# ch340c_esp32.net
KiCad netlist of a schematic drawn in EAGLE
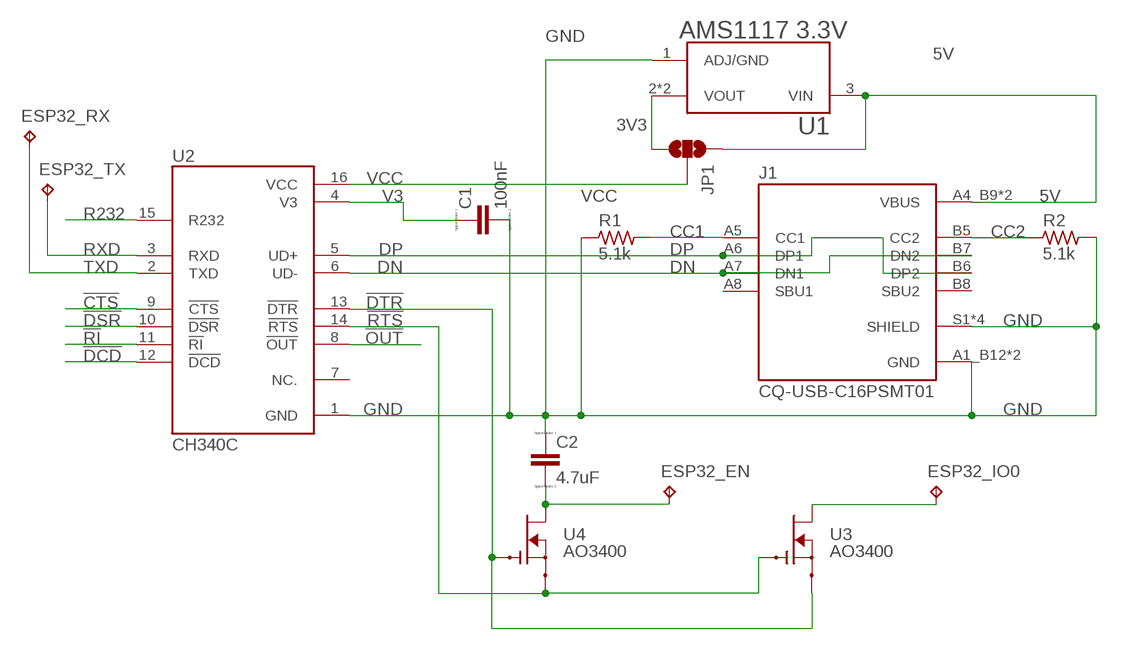
[diagram p0: schematic, sheet 1]

(export (version "E")
  (design (tool "Eeschema 10.0.6"))
  (components
    (comp (ref "C1")
      (value "100nF")
      (footprint "eagle-import:C0603")
      (libsource (lib "eagle-import") (part "CC0603"))
    )
    (comp (ref "C2")
      (value "4.7uF")
      (footprint "eagle-import:C0603")
      (libsource (lib "eagle-import") (part "CC0603"))
    )
    (comp (ref "ESP32_EN")
      (value "TPB1,27")
      (footprint "eagle-import:B1,27")
      (libsource (lib "eagle-import") (part "TPB1,27"))
    )
    (comp (ref "ESP32_IO0")
      (value "TPB1,27")
      (footprint "eagle-import:B1,27")
      (libsource (lib "eagle-import") (part "TPB1,27"))
    )
    (comp (ref "ESP32_RX")
      (value "TPB1,27")
      (footprint "eagle-import:B1,27")
      (libsource (lib "eagle-import") (part "TPB1,27"))
    )
    (comp (ref "ESP32_TX")
      (value "TPB1,27")
      (footprint "eagle-import:B1,27")
      (libsource (lib "eagle-import") (part "TPB1,27"))
    )
    (comp (ref "J1")
      (value "CQ-USB-C16PSMT01")
      (footprint "eagle-import:SHENZHEN-CHUANGQIN-TECHNOLOGY_CQ-USB-C16PSMT01")
      (fields (field (name "MF") "Shenzen Chuangqin Technology"))
      (libsource (lib "eagle-import") (part "CQ-USB-C16PSMT01"))
    )
    (comp (ref "JP1")
      (value "JUMPER-SMT_3_NO_NO-SILK")
      (footprint "eagle-import:SMT-JUMPER_3_NO_NO-SILK")
      (libsource (lib "eagle-import") (part "JUMPER-SMT_3_NO_NO-SILK"))
    )
    (comp (ref "R1")
      (value "5.1k")
      (footprint "eagle-import:RC-MASTER-SMD_R0603MP")
      (libsource (lib "eagle-import") (part "RC-MASTER-SMD_R_0603MP"))
    )
    (comp (ref "R2")
      (value "5.1k")
      (footprint "eagle-import:RC-MASTER-SMD_R0603MP")
      (libsource (lib "eagle-import") (part "RC-MASTER-SMD_R_0603MP"))
    )
    (comp (ref "U1")
      (value "AMS1117 3.3V")
      (footprint "eagle-import:SOT229P700X180-4N")
      (fields (field (name "MF") "Advanced Monolithic Systems") (field (name "MP") "AMS1117"))
      (libsource (lib "eagle-import") (part "AMS1117"))
    )
    (comp (ref "U2")
      (value "CH340C")
      (footprint "eagle-import:SOIC127P600X180-16N")
      (fields (field (name "MF") "WCH"))
      (libsource (lib "eagle-import") (part "CH340C"))
    )
    (comp (ref "U3")
      (value "AO3400")
      (footprint "eagle-import:SOT23")
      (fields (field (name "MF") "Alpha &"))
      (libsource (lib "eagle-import") (part "AO3400"))
    )
    (comp (ref "U4")
      (value "AO3400")
      (footprint "eagle-import:SOT23")
      (fields (field (name "MF") "Alpha &"))
      (libsource (lib "eagle-import") (part "AO3400"))
    )
  )
  (nets
    (net (code "1") (name "/3V3") (class "Default")
      (node (ref "JP1") (pin "1") (pinfunction "1_1") (pintype "passive"))
      (node (ref "U1") (pin "2") (pinfunction "VOUT_2") (pintype "output"))
      (node (ref "U1") (pin "4") (pinfunction "VOUT_4") (pintype "output"))
    )
    (net (code "2") (name "/5V") (class "Default")
      (node (ref "J1") (pin "A4_B9") (pinfunction "VBUS_A4_B9") (pintype "power_in"))
      (node (ref "J1") (pin "B4_A9") (pinfunction "VBUS_B4_A9") (pintype "power_in"))
      (node (ref "JP1") (pin "3") (pinfunction "3_3") (pintype "passive"))
      (node (ref "U1") (pin "3") (pinfunction "VIN_3") (pintype "input"))
    )
    (net (code "3") (name "/CC1") (class "Default")
      (node (ref "J1") (pin "A5") (pinfunction "CC1_A5") (pintype "bidirectional"))
      (node (ref "R1") (pin "2") (pinfunction "2_2") (pintype "passive"))
    )
    (net (code "4") (name "/CC2") (class "Default")
      (node (ref "J1") (pin "B5") (pinfunction "CC2_B5") (pintype "bidirectional"))
      (node (ref "R2") (pin "1") (pinfunction "1_1") (pintype "passive"))
    )
    (net (code "5") (name "/DN") (class "Default")
      (node (ref "J1") (pin "A7") (pinfunction "DN1_A7") (pintype "bidirectional"))
      (node (ref "J1") (pin "B7") (pinfunction "DN2_B7") (pintype "bidirectional"))
      (node (ref "U2") (pin "6") (pinfunction "UD-_6") (pintype "bidirectional"))
    )
    (net (code "6") (name "/DP") (class "Default")
      (node (ref "J1") (pin "A6") (pinfunction "DP1_A6") (pintype "bidirectional"))
      (node (ref "J1") (pin "B6") (pinfunction "DP2_B6") (pintype "bidirectional"))
      (node (ref "U2") (pin "5") (pinfunction "UD+_5") (pintype "bidirectional"))
    )
    (net (code "7") (name "/GND") (class "Default")
      (node (ref "C1") (pin "2") (pinfunction "2_2") (pintype "passive"))
      (node (ref "C2") (pin "1") (pinfunction "1_1") (pintype "passive"))
      (node (ref "J1") (pin "A1_B12") (pinfunction "GND_A1_B12") (pintype "power_in"))
      (node (ref "J1") (pin "B1_A12") (pinfunction "GND_B1_A12") (pintype "power_in"))
      (node (ref "J1") (pin "S1") (pinfunction "SHIELD_S1") (pintype "passive"))
      (node (ref "J1") (pin "S2") (pinfunction "SHIELD_S2") (pintype "passive"))
      (node (ref "J1") (pin "S3") (pinfunction "SHIELD_S3") (pintype "passive"))
      (node (ref "J1") (pin "S4") (pinfunction "SHIELD_S4") (pintype "passive"))
      (node (ref "R1") (pin "1") (pinfunction "1_1") (pintype "passive"))
      (node (ref "R2") (pin "2") (pinfunction "2_2") (pintype "passive"))
      (node (ref "U1") (pin "1") (pinfunction "ADJ/GND_1") (pintype "power_in"))
      (node (ref "U2") (pin "1") (pinfunction "GND_1") (pintype "power_in"))
    )
    (net (code "8") (name "/R232") (class "Default")
      (node (ref "U2") (pin "15") (pinfunction "R232_15") (pintype "input"))
    )
    (net (code "9") (name "/RXD") (class "Default")
      (node (ref "ESP32_TX") (pin "TP") (pinfunction "TP_TP") (pintype "input"))
      (node (ref "U2") (pin "3") (pinfunction "RXD_3") (pintype "input"))
    )
    (net (code "10") (name "/TXD") (class "Default")
      (node (ref "ESP32_RX") (pin "TP") (pinfunction "TP_TP") (pintype "input"))
      (node (ref "U2") (pin "2") (pinfunction "TXD_2") (pintype "output"))
    )
    (net (code "11") (name "/V3") (class "Default")
      (node (ref "C1") (pin "1") (pinfunction "1_1") (pintype "passive"))
      (node (ref "U2") (pin "4") (pinfunction "V3_4") (pintype "power_in"))
    )
    (net (code "12") (name "/VCC") (class "Default")
      (node (ref "JP1") (pin "2") (pinfunction "2_2") (pintype "passive"))
      (node (ref "U2") (pin "16") (pinfunction "VCC_16") (pintype "power_in"))
    )
    (net (code "13") (name "/~{CTS}") (class "Default")
      (node (ref "U2") (pin "9") (pinfunction "~{CTS}_9") (pintype "input"))
    )
    (net (code "14") (name "/~{DCD}") (class "Default")
      (node (ref "U2") (pin "12") (pinfunction "~{DCD}_12") (pintype "input"))
    )
    (net (code "15") (name "/~{DSR}") (class "Default")
      (node (ref "U2") (pin "10") (pinfunction "~{DSR}_10") (pintype "input"))
    )
    (net (code "16") (name "/~{DTR}") (class "Default")
      (node (ref "U2") (pin "13") (pinfunction "~{DTR}_13") (pintype "output"))
      (node (ref "U3") (pin "2") (pinfunction "S_2") (pintype "passive"))
      (node (ref "U4") (pin "1") (pinfunction "G_1") (pintype "passive"))
    )
    (net (code "17") (name "/~{OUT}") (class "Default")
      (node (ref "U2") (pin "8") (pinfunction "~{OUT}_8") (pintype "output"))
    )
    (net (code "18") (name "/~{RI}") (class "Default")
      (node (ref "U2") (pin "11") (pinfunction "~{RI}_11") (pintype "input"))
    )
    (net (code "19") (name "/~{RTS}") (class "Default")
      (node (ref "U2") (pin "14") (pinfunction "~{RTS}_14") (pintype "output"))
      (node (ref "U3") (pin "1") (pinfunction "G_1") (pintype "passive"))
      (node (ref "U4") (pin "2") (pinfunction "S_2") (pintype "passive"))
    )
    (net (code "20") (name "Net-(U3-D)") (class "Default")
      (node (ref "ESP32_IO0") (pin "TP") (pinfunction "TP_TP") (pintype "input"))
      (node (ref "U3") (pin "3") (pinfunction "D_3") (pintype "passive"))
    )
    (net (code "21") (name "Net-(U4-D)") (class "Default")
      (node (ref "C2") (pin "2") (pinfunction "2_2") (pintype "passive"))
      (node (ref "ESP32_EN") (pin "TP") (pinfunction "TP_TP") (pintype "input"))
      (node (ref "U4") (pin "3") (pinfunction "D_3") (pintype "passive"))
    )
    (net (code "22") (name "unconnected-(J1-SBU1-PadA8)") (class "Default")
      (node (ref "J1") (pin "A8") (pinfunction "SBU1_A8") (pintype "bidirectional"))
    )
    (net (code "23") (name "unconnected-(J1-SBU2-PadB8)") (class "Default")
      (node (ref "J1") (pin "B8") (pinfunction "SBU2_B8") (pintype "bidirectional"))
    )
    (net (code "24") (name "unconnected-(U2-NC.-Pad7)") (class "Default")
      (node (ref "U2") (pin "7") (pinfunction "NC._7") (pintype "no_connect"))
    )
  )
)
